# seven_segment_2.net
KiCad netlist of a schematic drawn in EAGLE
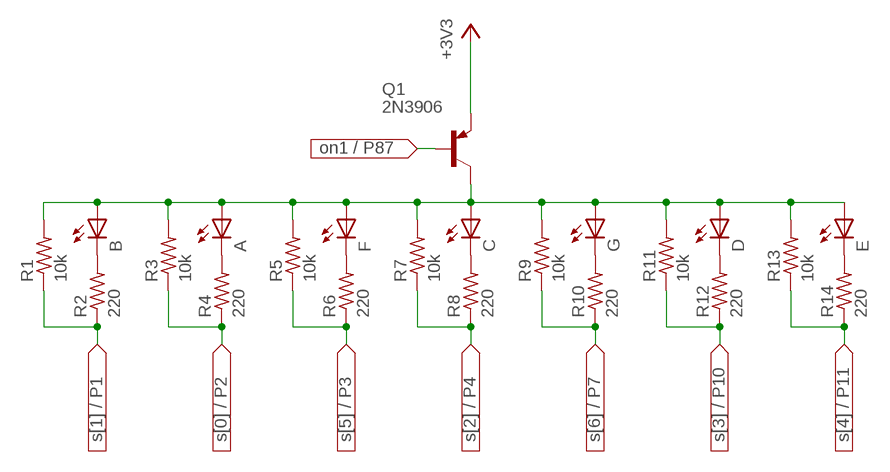
[diagram p0: schematic, sheet 1]

(export (version "E")
  (design (tool "Eeschema 10.0.6"))
  (components
    (comp (ref "A")
      (value "LED5MM")
      (footprint "eagle-import:LED5MM")
      (libsource (lib "eagle-import") (part "LED5MM"))
    )
    (comp (ref "B")
      (value "LED5MM")
      (footprint "eagle-import:LED5MM")
      (libsource (lib "eagle-import") (part "LED5MM"))
    )
    (comp (ref "C")
      (value "LED5MM")
      (footprint "eagle-import:LED5MM")
      (libsource (lib "eagle-import") (part "LED5MM"))
    )
    (comp (ref "D")
      (value "LED5MM")
      (footprint "eagle-import:LED5MM")
      (libsource (lib "eagle-import") (part "LED5MM"))
    )
    (comp (ref "E")
      (value "LED5MM")
      (footprint "eagle-import:LED5MM")
      (libsource (lib "eagle-import") (part "LED5MM"))
    )
    (comp (ref "F")
      (value "LED5MM")
      (footprint "eagle-import:LED5MM")
      (libsource (lib "eagle-import") (part "LED5MM"))
    )
    (comp (ref "G")
      (value "LED5MM")
      (footprint "eagle-import:LED5MM")
      (libsource (lib "eagle-import") (part "LED5MM"))
    )
    (comp (ref "Q1")
      (value "2N3906")
      (footprint "eagle-import:TO92")
      (libsource (lib "eagle-import") (part "2N3906"))
    )
    (comp (ref "R1")
      (value "10k")
      (footprint "eagle-import:0411_12")
      (libsource (lib "eagle-import") (part "R-US_0411/12"))
    )
    (comp (ref "R2")
      (value "220")
      (footprint "eagle-import:0411_12")
      (libsource (lib "eagle-import") (part "R-US_0411/12"))
    )
    (comp (ref "R3")
      (value "10k")
      (footprint "eagle-import:0411_12")
      (libsource (lib "eagle-import") (part "R-US_0411/12"))
    )
    (comp (ref "R4")
      (value "220")
      (footprint "eagle-import:0411_12")
      (libsource (lib "eagle-import") (part "R-US_0411/12"))
    )
    (comp (ref "R5")
      (value "10k")
      (footprint "eagle-import:0411_12")
      (libsource (lib "eagle-import") (part "R-US_0411/12"))
    )
    (comp (ref "R6")
      (value "220")
      (footprint "eagle-import:0411_12")
      (libsource (lib "eagle-import") (part "R-US_0411/12"))
    )
    (comp (ref "R7")
      (value "10k")
      (footprint "eagle-import:0411_12")
      (libsource (lib "eagle-import") (part "R-US_0411/12"))
    )
    (comp (ref "R8")
      (value "220")
      (footprint "eagle-import:0411_12")
      (libsource (lib "eagle-import") (part "R-US_0411/12"))
    )
    (comp (ref "R9")
      (value "10k")
      (footprint "eagle-import:0411_12")
      (libsource (lib "eagle-import") (part "R-US_0411/12"))
    )
    (comp (ref "R10")
      (value "220")
      (footprint "eagle-import:0411_12")
      (libsource (lib "eagle-import") (part "R-US_0411/12"))
    )
    (comp (ref "R11")
      (value "10k")
      (footprint "eagle-import:0411_12")
      (libsource (lib "eagle-import") (part "R-US_0411/12"))
    )
    (comp (ref "R12")
      (value "220")
      (footprint "eagle-import:0411_12")
      (libsource (lib "eagle-import") (part "R-US_0411/12"))
    )
    (comp (ref "R13")
      (value "10k")
      (footprint "eagle-import:0411_12")
      (libsource (lib "eagle-import") (part "R-US_0411/12"))
    )
    (comp (ref "R14")
      (value "220")
      (footprint "eagle-import:0411_12")
      (libsource (lib "eagle-import") (part "R-US_0411/12"))
    )
  )
  (nets
    (net (code "1") (name "+3V3") (class "Default")
      (node (ref "Q1") (pin "3") (pinfunction "E_3") (pintype "passive"))
    )
    (net (code "2") (name "Net-(A-C)") (class "Default")
      (node (ref "A") (pin "K") (pinfunction "C_K") (pintype "passive"))
      (node (ref "R4") (pin "2") (pinfunction "2_2") (pintype "passive"))
    )
    (net (code "3") (name "Net-(B-C)") (class "Default")
      (node (ref "B") (pin "K") (pinfunction "C_K") (pintype "passive"))
      (node (ref "R2") (pin "2") (pinfunction "2_2") (pintype "passive"))
    )
    (net (code "4") (name "Net-(C-C)") (class "Default")
      (node (ref "C") (pin "K") (pinfunction "C_K") (pintype "passive"))
      (node (ref "R8") (pin "2") (pinfunction "2_2") (pintype "passive"))
    )
    (net (code "5") (name "Net-(D-C)") (class "Default")
      (node (ref "D") (pin "K") (pinfunction "C_K") (pintype "passive"))
      (node (ref "R12") (pin "2") (pinfunction "2_2") (pintype "passive"))
    )
    (net (code "6") (name "Net-(E-C)") (class "Default")
      (node (ref "E") (pin "K") (pinfunction "C_K") (pintype "passive"))
      (node (ref "R14") (pin "2") (pinfunction "2_2") (pintype "passive"))
    )
    (net (code "7") (name "Net-(F-C)") (class "Default")
      (node (ref "F") (pin "K") (pinfunction "C_K") (pintype "passive"))
      (node (ref "R6") (pin "2") (pinfunction "2_2") (pintype "passive"))
    )
    (net (code "8") (name "Net-(G-C)") (class "Default")
      (node (ref "G") (pin "K") (pinfunction "C_K") (pintype "passive"))
      (node (ref "R10") (pin "2") (pinfunction "2_2") (pintype "passive"))
    )
    (net (code "9") (name "Net-(Q1-C)") (class "Default")
      (node (ref "A") (pin "A") (pinfunction "A_A") (pintype "passive"))
      (node (ref "B") (pin "A") (pinfunction "A_A") (pintype "passive"))
      (node (ref "C") (pin "A") (pinfunction "A_A") (pintype "passive"))
      (node (ref "D") (pin "A") (pinfunction "A_A") (pintype "passive"))
      (node (ref "E") (pin "A") (pinfunction "A_A") (pintype "passive"))
      (node (ref "F") (pin "A") (pinfunction "A_A") (pintype "passive"))
      (node (ref "G") (pin "A") (pinfunction "A_A") (pintype "passive"))
      (node (ref "Q1") (pin "1") (pinfunction "C_1") (pintype "passive"))
      (node (ref "R1") (pin "2") (pinfunction "2_2") (pintype "passive"))
      (node (ref "R11") (pin "2") (pinfunction "2_2") (pintype "passive"))
      (node (ref "R13") (pin "2") (pinfunction "2_2") (pintype "passive"))
      (node (ref "R3") (pin "2") (pinfunction "2_2") (pintype "passive"))
      (node (ref "R5") (pin "2") (pinfunction "2_2") (pintype "passive"))
      (node (ref "R7") (pin "2") (pinfunction "2_2") (pintype "passive"))
      (node (ref "R9") (pin "2") (pinfunction "2_2") (pintype "passive"))
    )
    (net (code "10") (name "Net-(R1-Pad1)") (class "Default")
      (node (ref "R1") (pin "1") (pinfunction "1_1") (pintype "passive"))
      (node (ref "R2") (pin "1") (pinfunction "1_1") (pintype "passive"))
    )
    (net (code "11") (name "Net-(R3-Pad1)") (class "Default")
      (node (ref "R3") (pin "1") (pinfunction "1_1") (pintype "passive"))
      (node (ref "R4") (pin "1") (pinfunction "1_1") (pintype "passive"))
    )
    (net (code "12") (name "Net-(R5-Pad1)") (class "Default")
      (node (ref "R5") (pin "1") (pinfunction "1_1") (pintype "passive"))
      (node (ref "R6") (pin "1") (pinfunction "1_1") (pintype "passive"))
    )
    (net (code "13") (name "Net-(R7-Pad1)") (class "Default")
      (node (ref "R7") (pin "1") (pinfunction "1_1") (pintype "passive"))
      (node (ref "R8") (pin "1") (pinfunction "1_1") (pintype "passive"))
    )
    (net (code "14") (name "Net-(R10-Pad1)") (class "Default")
      (node (ref "R10") (pin "1") (pinfunction "1_1") (pintype "passive"))
      (node (ref "R9") (pin "1") (pinfunction "1_1") (pintype "passive"))
    )
    (net (code "15") (name "Net-(R11-Pad1)") (class "Default")
      (node (ref "R11") (pin "1") (pinfunction "1_1") (pintype "passive"))
      (node (ref "R12") (pin "1") (pinfunction "1_1") (pintype "passive"))
    )
    (net (code "16") (name "Net-(R13-Pad1)") (class "Default")
      (node (ref "R13") (pin "1") (pinfunction "1_1") (pintype "passive"))
      (node (ref "R14") (pin "1") (pinfunction "1_1") (pintype "passive"))
    )
    (net (code "17") (name "unconnected-(Q1-B-Pad2)") (class "Default")
      (node (ref "Q1") (pin "2") (pinfunction "B_2") (pintype "passive"))
    )
  )
)
